# Scrum_Marquee.net
KiCad netlist of a schematic drawn in EAGLE
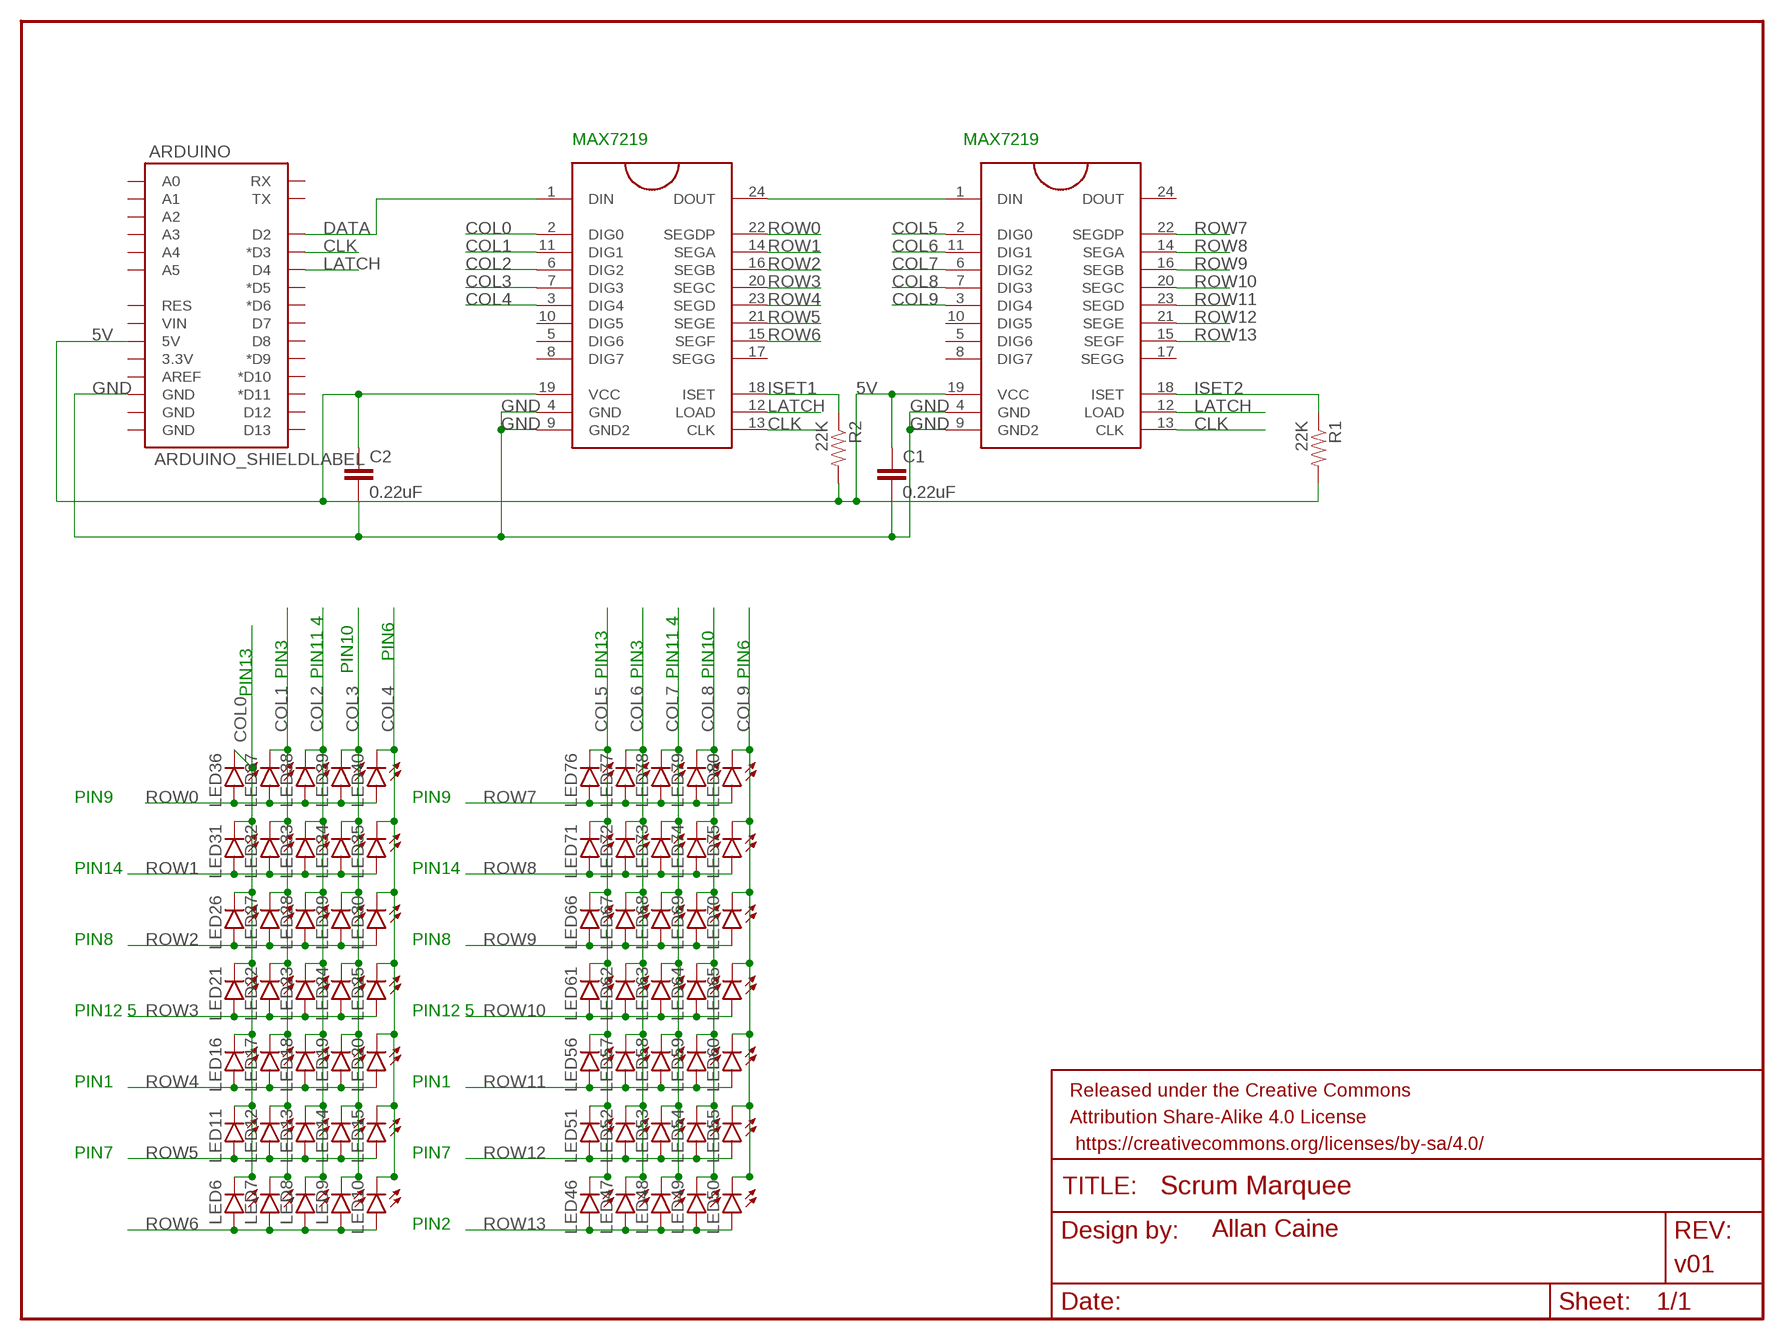
[diagram p0: schematic, sheet 1]

(export (version "E")
  (design (tool "Eeschema 10.0.6"))
  (components
    (comp (ref "ARDUINO")
      (value "ARDUINO_SHIELDLABEL")
      (footprint "eagle-import:DUEMILANOVE_SHIELD")
      (libsource (lib "eagle-import") (part "ARDUINO_SHIELDLABEL"))
    )
    (comp (ref "C1")
      (value "0.22uF")
      (footprint "eagle-import:CAP-PTH-SMALL-KIT")
      (libsource (lib "eagle-import") (part "0.1UF-50V-20%(PTH)KIT-EZ"))
    )
    (comp (ref "C2")
      (value "0.22uF")
      (footprint "eagle-import:CAP-PTH-SMALL-KIT")
      (libsource (lib "eagle-import") (part "0.1UF-50V-20%(PTH)KIT-EZ"))
    )
    (comp (ref "FRAME1")
      (value "FRAME-LETTER")
      (footprint "eagle-import:CREATIVE_COMMONS")
      (fields (field (name "DESIGNER") "Allan Caine"))
      (libsource (lib "eagle-import") (part "FRAME-LETTER"))
    )
    (comp (ref "LED6")
      (value "LED5MM")
      (footprint "eagle-import:LED5MM")
      (libsource (lib "eagle-import") (part "LED5MM"))
    )
    (comp (ref "LED7")
      (value "LED5MM")
      (footprint "eagle-import:LED5MM")
      (libsource (lib "eagle-import") (part "LED5MM"))
    )
    (comp (ref "LED8")
      (value "LED5MM")
      (footprint "eagle-import:LED5MM")
      (libsource (lib "eagle-import") (part "LED5MM"))
    )
    (comp (ref "LED9")
      (value "LED5MM")
      (footprint "eagle-import:LED5MM")
      (libsource (lib "eagle-import") (part "LED5MM"))
    )
    (comp (ref "LED10")
      (value "LED5MM")
      (footprint "eagle-import:LED5MM")
      (libsource (lib "eagle-import") (part "LED5MM"))
    )
    (comp (ref "LED11")
      (value "LED5MM")
      (footprint "eagle-import:LED5MM")
      (libsource (lib "eagle-import") (part "LED5MM"))
    )
    (comp (ref "LED12")
      (value "LED5MM")
      (footprint "eagle-import:LED5MM")
      (libsource (lib "eagle-import") (part "LED5MM"))
    )
    (comp (ref "LED13")
      (value "LED5MM")
      (footprint "eagle-import:LED5MM")
      (libsource (lib "eagle-import") (part "LED5MM"))
    )
    (comp (ref "LED14")
      (value "LED5MM")
      (footprint "eagle-import:LED5MM")
      (libsource (lib "eagle-import") (part "LED5MM"))
    )
    (comp (ref "LED15")
      (value "LED5MM")
      (footprint "eagle-import:LED5MM")
      (libsource (lib "eagle-import") (part "LED5MM"))
    )
    (comp (ref "LED16")
      (value "LED5MM")
      (footprint "eagle-import:LED5MM")
      (libsource (lib "eagle-import") (part "LED5MM"))
    )
    (comp (ref "LED17")
      (value "LED5MM")
      (footprint "eagle-import:LED5MM")
      (libsource (lib "eagle-import") (part "LED5MM"))
    )
    (comp (ref "LED18")
      (value "LED5MM")
      (footprint "eagle-import:LED5MM")
      (libsource (lib "eagle-import") (part "LED5MM"))
    )
    (comp (ref "LED19")
      (value "LED5MM")
      (footprint "eagle-import:LED5MM")
      (libsource (lib "eagle-import") (part "LED5MM"))
    )
    (comp (ref "LED20")
      (value "LED5MM")
      (footprint "eagle-import:LED5MM")
      (libsource (lib "eagle-import") (part "LED5MM"))
    )
    (comp (ref "LED21")
      (value "LED5MM")
      (footprint "eagle-import:LED5MM")
      (libsource (lib "eagle-import") (part "LED5MM"))
    )
    (comp (ref "LED22")
      (value "LED5MM")
      (footprint "eagle-import:LED5MM")
      (libsource (lib "eagle-import") (part "LED5MM"))
    )
    (comp (ref "LED23")
      (value "LED5MM")
      (footprint "eagle-import:LED5MM")
      (libsource (lib "eagle-import") (part "LED5MM"))
    )
    (comp (ref "LED24")
      (value "LED5MM")
      (footprint "eagle-import:LED5MM")
      (libsource (lib "eagle-import") (part "LED5MM"))
    )
    (comp (ref "LED25")
      (value "LED5MM")
      (footprint "eagle-import:LED5MM")
      (libsource (lib "eagle-import") (part "LED5MM"))
    )
    (comp (ref "LED26")
      (value "LED5MM")
      (footprint "eagle-import:LED5MM")
      (libsource (lib "eagle-import") (part "LED5MM"))
    )
    (comp (ref "LED27")
      (value "LED5MM")
      (footprint "eagle-import:LED5MM")
      (libsource (lib "eagle-import") (part "LED5MM"))
    )
    (comp (ref "LED28")
      (value "LED5MM")
      (footprint "eagle-import:LED5MM")
      (libsource (lib "eagle-import") (part "LED5MM"))
    )
    (comp (ref "LED29")
      (value "LED5MM")
      (footprint "eagle-import:LED5MM")
      (libsource (lib "eagle-import") (part "LED5MM"))
    )
    (comp (ref "LED30")
      (value "LED5MM")
      (footprint "eagle-import:LED5MM")
      (libsource (lib "eagle-import") (part "LED5MM"))
    )
    (comp (ref "LED31")
      (value "LED5MM")
      (footprint "eagle-import:LED5MM")
      (libsource (lib "eagle-import") (part "LED5MM"))
    )
    (comp (ref "LED32")
      (value "LED5MM")
      (footprint "eagle-import:LED5MM")
      (libsource (lib "eagle-import") (part "LED5MM"))
    )
    (comp (ref "LED33")
      (value "LED5MM")
      (footprint "eagle-import:LED5MM")
      (libsource (lib "eagle-import") (part "LED5MM"))
    )
    (comp (ref "LED34")
      (value "LED5MM")
      (footprint "eagle-import:LED5MM")
      (libsource (lib "eagle-import") (part "LED5MM"))
    )
    (comp (ref "LED35")
      (value "LED5MM")
      (footprint "eagle-import:LED5MM")
      (libsource (lib "eagle-import") (part "LED5MM"))
    )
    (comp (ref "LED36")
      (value "LED5MM")
      (footprint "eagle-import:LED5MM")
      (libsource (lib "eagle-import") (part "LED5MM"))
    )
    (comp (ref "LED37")
      (value "LED5MM")
      (footprint "eagle-import:LED5MM")
      (libsource (lib "eagle-import") (part "LED5MM"))
    )
    (comp (ref "LED38")
      (value "LED5MM")
      (footprint "eagle-import:LED5MM")
      (libsource (lib "eagle-import") (part "LED5MM"))
    )
    (comp (ref "LED39")
      (value "LED5MM")
      (footprint "eagle-import:LED5MM")
      (libsource (lib "eagle-import") (part "LED5MM"))
    )
    (comp (ref "LED40")
      (value "LED5MM")
      (footprint "eagle-import:LED5MM")
      (libsource (lib "eagle-import") (part "LED5MM"))
    )
    (comp (ref "LED46")
      (value "LED5MM")
      (footprint "eagle-import:LED5MM")
      (libsource (lib "eagle-import") (part "LED5MM"))
    )
    (comp (ref "LED47")
      (value "LED5MM")
      (footprint "eagle-import:LED5MM")
      (libsource (lib "eagle-import") (part "LED5MM"))
    )
    (comp (ref "LED48")
      (value "LED5MM")
      (footprint "eagle-import:LED5MM")
      (libsource (lib "eagle-import") (part "LED5MM"))
    )
    (comp (ref "LED49")
      (value "LED5MM")
      (footprint "eagle-import:LED5MM")
      (libsource (lib "eagle-import") (part "LED5MM"))
    )
    (comp (ref "LED50")
      (value "LED5MM")
      (footprint "eagle-import:LED5MM")
      (libsource (lib "eagle-import") (part "LED5MM"))
    )
    (comp (ref "LED51")
      (value "LED5MM")
      (footprint "eagle-import:LED5MM")
      (libsource (lib "eagle-import") (part "LED5MM"))
    )
    (comp (ref "LED52")
      (value "LED5MM")
      (footprint "eagle-import:LED5MM")
      (libsource (lib "eagle-import") (part "LED5MM"))
    )
    (comp (ref "LED53")
      (value "LED5MM")
      (footprint "eagle-import:LED5MM")
      (libsource (lib "eagle-import") (part "LED5MM"))
    )
    (comp (ref "LED54")
      (value "LED5MM")
      (footprint "eagle-import:LED5MM")
      (libsource (lib "eagle-import") (part "LED5MM"))
    )
    (comp (ref "LED55")
      (value "LED5MM")
      (footprint "eagle-import:LED5MM")
      (libsource (lib "eagle-import") (part "LED5MM"))
    )
    (comp (ref "LED56")
      (value "LED5MM")
      (footprint "eagle-import:LED5MM")
      (libsource (lib "eagle-import") (part "LED5MM"))
    )
    (comp (ref "LED57")
      (value "LED5MM")
      (footprint "eagle-import:LED5MM")
      (libsource (lib "eagle-import") (part "LED5MM"))
    )
    (comp (ref "LED58")
      (value "LED5MM")
      (footprint "eagle-import:LED5MM")
      (libsource (lib "eagle-import") (part "LED5MM"))
    )
    (comp (ref "LED59")
      (value "LED5MM")
      (footprint "eagle-import:LED5MM")
      (libsource (lib "eagle-import") (part "LED5MM"))
    )
    (comp (ref "LED60")
      (value "LED5MM")
      (footprint "eagle-import:LED5MM")
      (libsource (lib "eagle-import") (part "LED5MM"))
    )
    (comp (ref "LED61")
      (value "LED5MM")
      (footprint "eagle-import:LED5MM")
      (libsource (lib "eagle-import") (part "LED5MM"))
    )
    (comp (ref "LED62")
      (value "LED5MM")
      (footprint "eagle-import:LED5MM")
      (libsource (lib "eagle-import") (part "LED5MM"))
    )
    (comp (ref "LED63")
      (value "LED5MM")
      (footprint "eagle-import:LED5MM")
      (libsource (lib "eagle-import") (part "LED5MM"))
    )
    (comp (ref "LED64")
      (value "LED5MM")
      (footprint "eagle-import:LED5MM")
      (libsource (lib "eagle-import") (part "LED5MM"))
    )
    (comp (ref "LED65")
      (value "LED5MM")
      (footprint "eagle-import:LED5MM")
      (libsource (lib "eagle-import") (part "LED5MM"))
    )
    (comp (ref "LED66")
      (value "LED5MM")
      (footprint "eagle-import:LED5MM")
      (libsource (lib "eagle-import") (part "LED5MM"))
    )
    (comp (ref "LED67")
      (value "LED5MM")
      (footprint "eagle-import:LED5MM")
      (libsource (lib "eagle-import") (part "LED5MM"))
    )
    (comp (ref "LED68")
      (value "LED5MM")
      (footprint "eagle-import:LED5MM")
      (libsource (lib "eagle-import") (part "LED5MM"))
    )
    (comp (ref "LED69")
      (value "LED5MM")
      (footprint "eagle-import:LED5MM")
      (libsource (lib "eagle-import") (part "LED5MM"))
    )
    (comp (ref "LED70")
      (value "LED5MM")
      (footprint "eagle-import:LED5MM")
      (libsource (lib "eagle-import") (part "LED5MM"))
    )
    (comp (ref "LED71")
      (value "LED5MM")
      (footprint "eagle-import:LED5MM")
      (libsource (lib "eagle-import") (part "LED5MM"))
    )
    (comp (ref "LED72")
      (value "LED5MM")
      (footprint "eagle-import:LED5MM")
      (libsource (lib "eagle-import") (part "LED5MM"))
    )
    (comp (ref "LED73")
      (value "LED5MM")
      (footprint "eagle-import:LED5MM")
      (libsource (lib "eagle-import") (part "LED5MM"))
    )
    (comp (ref "LED74")
      (value "LED5MM")
      (footprint "eagle-import:LED5MM")
      (libsource (lib "eagle-import") (part "LED5MM"))
    )
    (comp (ref "LED75")
      (value "LED5MM")
      (footprint "eagle-import:LED5MM")
      (libsource (lib "eagle-import") (part "LED5MM"))
    )
    (comp (ref "LED76")
      (value "LED5MM")
      (footprint "eagle-import:LED5MM")
      (libsource (lib "eagle-import") (part "LED5MM"))
    )
    (comp (ref "LED77")
      (value "LED5MM")
      (footprint "eagle-import:LED5MM")
      (libsource (lib "eagle-import") (part "LED5MM"))
    )
    (comp (ref "LED78")
      (value "LED5MM")
      (footprint "eagle-import:LED5MM")
      (libsource (lib "eagle-import") (part "LED5MM"))
    )
    (comp (ref "LED79")
      (value "LED5MM")
      (footprint "eagle-import:LED5MM")
      (libsource (lib "eagle-import") (part "LED5MM"))
    )
    (comp (ref "LED80")
      (value "LED5MM")
      (footprint "eagle-import:LED5MM")
      (libsource (lib "eagle-import") (part "LED5MM"))
    )
    (comp (ref "MAX7219DIP")
      (value "MAX7219DIP")
      (footprint "eagle-import:DIL24")
      (libsource (lib "eagle-import") (part "MAX7219DIP"))
    )
    (comp (ref "R1")
      (value "22K")
      (footprint "eagle-import:AXIAL-0.4")
      (libsource (lib "eagle-import") (part "RESISTORPTH-1/4W"))
    )
    (comp (ref "R2")
      (value "22K")
      (footprint "eagle-import:AXIAL-0.4")
      (libsource (lib "eagle-import") (part "RESISTORPTH-1/4W"))
    )
    (comp (ref "U$2")
      (value "MAX7219DIP")
      (footprint "eagle-import:DIL24")
      (libsource (lib "eagle-import") (part "MAX7219DIP"))
    )
  )
  (nets
    (net (code "1") (name "/5V") (class "Default")
      (node (ref "ARDUINO") (pin "5V") (pinfunction "5V_5V") (pintype "bidirectional"))
      (node (ref "C1") (pin "1") (pinfunction "1_1") (pintype "passive"))
      (node (ref "C2") (pin "1") (pinfunction "1_1") (pintype "passive"))
      (node (ref "MAX7219DIP") (pin "19") (pinfunction "VCC_19") (pintype "bidirectional"))
      (node (ref "R1") (pin "P$2") (pinfunction "2_P$2") (pintype "passive"))
      (node (ref "R2") (pin "P$2") (pinfunction "2_P$2") (pintype "passive"))
      (node (ref "U$2") (pin "19") (pinfunction "VCC_19") (pintype "bidirectional"))
    )
    (net (code "2") (name "/CLK") (class "Default")
      (node (ref "ARDUINO") (pin "D3") (pinfunction "*D3_D3") (pintype "bidirectional"))
      (node (ref "MAX7219DIP") (pin "13") (pinfunction "CLK_13") (pintype "bidirectional"))
      (node (ref "U$2") (pin "13") (pinfunction "CLK_13") (pintype "bidirectional"))
    )
    (net (code "3") (name "/COL0") (class "Default")
      (node (ref "LED11") (pin "K") (pinfunction "C_K") (pintype "passive"))
      (node (ref "LED16") (pin "K") (pinfunction "C_K") (pintype "passive"))
      (node (ref "LED21") (pin "K") (pinfunction "C_K") (pintype "passive"))
      (node (ref "LED26") (pin "K") (pinfunction "C_K") (pintype "passive"))
      (node (ref "LED31") (pin "K") (pinfunction "C_K") (pintype "passive"))
      (node (ref "LED36") (pin "K") (pinfunction "C_K") (pintype "passive"))
      (node (ref "LED6") (pin "K") (pinfunction "C_K") (pintype "passive"))
      (node (ref "MAX7219DIP") (pin "2") (pinfunction "DIG0_2") (pintype "bidirectional"))
    )
    (net (code "4") (name "/COL1") (class "Default")
      (node (ref "LED12") (pin "K") (pinfunction "C_K") (pintype "passive"))
      (node (ref "LED17") (pin "K") (pinfunction "C_K") (pintype "passive"))
      (node (ref "LED22") (pin "K") (pinfunction "C_K") (pintype "passive"))
      (node (ref "LED27") (pin "K") (pinfunction "C_K") (pintype "passive"))
      (node (ref "LED32") (pin "K") (pinfunction "C_K") (pintype "passive"))
      (node (ref "LED37") (pin "K") (pinfunction "C_K") (pintype "passive"))
      (node (ref "LED7") (pin "K") (pinfunction "C_K") (pintype "passive"))
      (node (ref "MAX7219DIP") (pin "11") (pinfunction "DIG1_11") (pintype "bidirectional"))
    )
    (net (code "5") (name "/COL2") (class "Default")
      (node (ref "LED13") (pin "K") (pinfunction "C_K") (pintype "passive"))
      (node (ref "LED18") (pin "K") (pinfunction "C_K") (pintype "passive"))
      (node (ref "LED23") (pin "K") (pinfunction "C_K") (pintype "passive"))
      (node (ref "LED28") (pin "K") (pinfunction "C_K") (pintype "passive"))
      (node (ref "LED33") (pin "K") (pinfunction "C_K") (pintype "passive"))
      (node (ref "LED38") (pin "K") (pinfunction "C_K") (pintype "passive"))
      (node (ref "LED8") (pin "K") (pinfunction "C_K") (pintype "passive"))
      (node (ref "MAX7219DIP") (pin "6") (pinfunction "DIG2_6") (pintype "bidirectional"))
    )
    (net (code "6") (name "/COL3") (class "Default")
      (node (ref "LED14") (pin "K") (pinfunction "C_K") (pintype "passive"))
      (node (ref "LED19") (pin "K") (pinfunction "C_K") (pintype "passive"))
      (node (ref "LED24") (pin "K") (pinfunction "C_K") (pintype "passive"))
      (node (ref "LED29") (pin "K") (pinfunction "C_K") (pintype "passive"))
      (node (ref "LED34") (pin "K") (pinfunction "C_K") (pintype "passive"))
      (node (ref "LED39") (pin "K") (pinfunction "C_K") (pintype "passive"))
      (node (ref "LED9") (pin "K") (pinfunction "C_K") (pintype "passive"))
      (node (ref "MAX7219DIP") (pin "7") (pinfunction "DIG3_7") (pintype "bidirectional"))
    )
    (net (code "7") (name "/COL4") (class "Default")
      (node (ref "LED10") (pin "K") (pinfunction "C_K") (pintype "passive"))
      (node (ref "LED15") (pin "K") (pinfunction "C_K") (pintype "passive"))
      (node (ref "LED20") (pin "K") (pinfunction "C_K") (pintype "passive"))
      (node (ref "LED25") (pin "K") (pinfunction "C_K") (pintype "passive"))
      (node (ref "LED30") (pin "K") (pinfunction "C_K") (pintype "passive"))
      (node (ref "LED35") (pin "K") (pinfunction "C_K") (pintype "passive"))
      (node (ref "LED40") (pin "K") (pinfunction "C_K") (pintype "passive"))
      (node (ref "MAX7219DIP") (pin "3") (pinfunction "DIG4_3") (pintype "bidirectional"))
    )
    (net (code "8") (name "/COL5") (class "Default")
      (node (ref "LED46") (pin "K") (pinfunction "C_K") (pintype "passive"))
      (node (ref "LED51") (pin "K") (pinfunction "C_K") (pintype "passive"))
      (node (ref "LED56") (pin "K") (pinfunction "C_K") (pintype "passive"))
      (node (ref "LED61") (pin "K") (pinfunction "C_K") (pintype "passive"))
      (node (ref "LED66") (pin "K") (pinfunction "C_K") (pintype "passive"))
      (node (ref "LED71") (pin "K") (pinfunction "C_K") (pintype "passive"))
      (node (ref "LED76") (pin "K") (pinfunction "C_K") (pintype "passive"))
      (node (ref "U$2") (pin "2") (pinfunction "DIG0_2") (pintype "bidirectional"))
    )
    (net (code "9") (name "/COL6") (class "Default")
      (node (ref "LED47") (pin "K") (pinfunction "C_K") (pintype "passive"))
      (node (ref "LED52") (pin "K") (pinfunction "C_K") (pintype "passive"))
      (node (ref "LED57") (pin "K") (pinfunction "C_K") (pintype "passive"))
      (node (ref "LED62") (pin "K") (pinfunction "C_K") (pintype "passive"))
      (node (ref "LED67") (pin "K") (pinfunction "C_K") (pintype "passive"))
      (node (ref "LED72") (pin "K") (pinfunction "C_K") (pintype "passive"))
      (node (ref "LED77") (pin "K") (pinfunction "C_K") (pintype "passive"))
      (node (ref "U$2") (pin "11") (pinfunction "DIG1_11") (pintype "bidirectional"))
    )
    (net (code "10") (name "/COL7") (class "Default")
      (node (ref "LED48") (pin "K") (pinfunction "C_K") (pintype "passive"))
      (node (ref "LED53") (pin "K") (pinfunction "C_K") (pintype "passive"))
      (node (ref "LED58") (pin "K") (pinfunction "C_K") (pintype "passive"))
      (node (ref "LED63") (pin "K") (pinfunction "C_K") (pintype "passive"))
      (node (ref "LED68") (pin "K") (pinfunction "C_K") (pintype "passive"))
      (node (ref "LED73") (pin "K") (pinfunction "C_K") (pintype "passive"))
      (node (ref "LED78") (pin "K") (pinfunction "C_K") (pintype "passive"))
      (node (ref "U$2") (pin "6") (pinfunction "DIG2_6") (pintype "bidirectional"))
    )
    (net (code "11") (name "/COL8") (class "Default")
      (node (ref "LED49") (pin "K") (pinfunction "C_K") (pintype "passive"))
      (node (ref "LED54") (pin "K") (pinfunction "C_K") (pintype "passive"))
      (node (ref "LED59") (pin "K") (pinfunction "C_K") (pintype "passive"))
      (node (ref "LED64") (pin "K") (pinfunction "C_K") (pintype "passive"))
      (node (ref "LED69") (pin "K") (pinfunction "C_K") (pintype "passive"))
      (node (ref "LED74") (pin "K") (pinfunction "C_K") (pintype "passive"))
      (node (ref "LED79") (pin "K") (pinfunction "C_K") (pintype "passive"))
      (node (ref "U$2") (pin "7") (pinfunction "DIG3_7") (pintype "bidirectional"))
    )
    (net (code "12") (name "/COL9") (class "Default")
      (node (ref "LED50") (pin "K") (pinfunction "C_K") (pintype "passive"))
      (node (ref "LED55") (pin "K") (pinfunction "C_K") (pintype "passive"))
      (node (ref "LED60") (pin "K") (pinfunction "C_K") (pintype "passive"))
      (node (ref "LED65") (pin "K") (pinfunction "C_K") (pintype "passive"))
      (node (ref "LED70") (pin "K") (pinfunction "C_K") (pintype "passive"))
      (node (ref "LED75") (pin "K") (pinfunction "C_K") (pintype "passive"))
      (node (ref "LED80") (pin "K") (pinfunction "C_K") (pintype "passive"))
      (node (ref "U$2") (pin "3") (pinfunction "DIG4_3") (pintype "bidirectional"))
    )
    (net (code "13") (name "/DATA") (class "Default")
      (node (ref "ARDUINO") (pin "D2") (pinfunction "D2_D2") (pintype "bidirectional"))
      (node (ref "MAX7219DIP") (pin "1") (pinfunction "DIN_1") (pintype "bidirectional"))
    )
    (net (code "14") (name "/GND") (class "Default")
      (node (ref "ARDUINO") (pin "GND@2") (pinfunction "GND_GND@2") (pintype "bidirectional"))
      (node (ref "C1") (pin "2") (pinfunction "2_2") (pintype "passive"))
      (node (ref "C2") (pin "2") (pinfunction "2_2") (pintype "passive"))
      (node (ref "MAX7219DIP") (pin "4") (pinfunction "GND_4") (pintype "bidirectional"))
      (node (ref "MAX7219DIP") (pin "9") (pinfunction "GND2_9") (pintype "bidirectional"))
      (node (ref "U$2") (pin "4") (pinfunction "GND_4") (pintype "bidirectional"))
      (node (ref "U$2") (pin "9") (pinfunction "GND2_9") (pintype "bidirectional"))
    )
    (net (code "15") (name "/ISET1") (class "Default")
      (node (ref "MAX7219DIP") (pin "18") (pinfunction "ISET_18") (pintype "bidirectional"))
      (node (ref "R2") (pin "P$1") (pinfunction "1_P$1") (pintype "passive"))
    )
    (net (code "16") (name "/ISET2") (class "Default")
      (node (ref "R1") (pin "P$1") (pinfunction "1_P$1") (pintype "passive"))
      (node (ref "U$2") (pin "18") (pinfunction "ISET_18") (pintype "bidirectional"))
    )
    (net (code "17") (name "/LATCH") (class "Default")
      (node (ref "ARDUINO") (pin "D4") (pinfunction "D4_D4") (pintype "bidirectional"))
      (node (ref "MAX7219DIP") (pin "12") (pinfunction "LOAD_12") (pintype "bidirectional"))
      (node (ref "U$2") (pin "12") (pinfunction "LOAD_12") (pintype "bidirectional"))
    )
    (net (code "18") (name "/ROW0") (class "Default")
      (node (ref "LED36") (pin "A") (pinfunction "A_A") (pintype "passive"))
      (node (ref "LED37") (pin "A") (pinfunction "A_A") (pintype "passive"))
      (node (ref "LED38") (pin "A") (pinfunction "A_A") (pintype "passive"))
      (node (ref "LED39") (pin "A") (pinfunction "A_A") (pintype "passive"))
      (node (ref "LED40") (pin "A") (pinfunction "A_A") (pintype "passive"))
      (node (ref "MAX7219DIP") (pin "22") (pinfunction "SEGDP_22") (pintype "bidirectional"))
    )
    (net (code "19") (name "/ROW1") (class "Default")
      (node (ref "LED31") (pin "A") (pinfunction "A_A") (pintype "passive"))
      (node (ref "LED32") (pin "A") (pinfunction "A_A") (pintype "passive"))
      (node (ref "LED33") (pin "A") (pinfunction "A_A") (pintype "passive"))
      (node (ref "LED34") (pin "A") (pinfunction "A_A") (pintype "passive"))
      (node (ref "LED35") (pin "A") (pinfunction "A_A") (pintype "passive"))
      (node (ref "MAX7219DIP") (pin "14") (pinfunction "SEGA_14") (pintype "bidirectional"))
    )
    (net (code "20") (name "/ROW2") (class "Default")
      (node (ref "LED26") (pin "A") (pinfunction "A_A") (pintype "passive"))
      (node (ref "LED27") (pin "A") (pinfunction "A_A") (pintype "passive"))
      (node (ref "LED28") (pin "A") (pinfunction "A_A") (pintype "passive"))
      (node (ref "LED29") (pin "A") (pinfunction "A_A") (pintype "passive"))
      (node (ref "LED30") (pin "A") (pinfunction "A_A") (pintype "passive"))
      (node (ref "MAX7219DIP") (pin "16") (pinfunction "SEGB_16") (pintype "bidirectional"))
    )
    (net (code "21") (name "/ROW3") (class "Default")
      (node (ref "LED21") (pin "A") (pinfunction "A_A") (pintype "passive"))
      (node (ref "LED22") (pin "A") (pinfunction "A_A") (pintype "passive"))
      (node (ref "LED23") (pin "A") (pinfunction "A_A") (pintype "passive"))
      (node (ref "LED24") (pin "A") (pinfunction "A_A") (pintype "passive"))
      (node (ref "LED25") (pin "A") (pinfunction "A_A") (pintype "passive"))
      (node (ref "MAX7219DIP") (pin "20") (pinfunction "SEGC_20") (pintype "bidirectional"))
    )
    (net (code "22") (name "/ROW4") (class "Default")
      (node (ref "LED16") (pin "A") (pinfunction "A_A") (pintype "passive"))
      (node (ref "LED17") (pin "A") (pinfunction "A_A") (pintype "passive"))
      (node (ref "LED18") (pin "A") (pinfunction "A_A") (pintype "passive"))
      (node (ref "LED19") (pin "A") (pinfunction "A_A") (pintype "passive"))
      (node (ref "LED20") (pin "A") (pinfunction "A_A") (pintype "passive"))
      (node (ref "MAX7219DIP") (pin "23") (pinfunction "SEGD_23") (pintype "bidirectional"))
    )
    (net (code "23") (name "/ROW5") (class "Default")
      (node (ref "LED11") (pin "A") (pinfunction "A_A") (pintype "passive"))
      (node (ref "LED12") (pin "A") (pinfunction "A_A") (pintype "passive"))
      (node (ref "LED13") (pin "A") (pinfunction "A_A") (pintype "passive"))
      (node (ref "LED14") (pin "A") (pinfunction "A_A") (pintype "passive"))
      (node (ref "LED15") (pin "A") (pinfunction "A_A") (pintype "passive"))
      (node (ref "MAX7219DIP") (pin "21") (pinfunction "SEGE_21") (pintype "bidirectional"))
    )
    (net (code "24") (name "/ROW6") (class "Default")
      (node (ref "LED10") (pin "A") (pinfunction "A_A") (pintype "passive"))
      (node (ref "LED6") (pin "A") (pinfunction "A_A") (pintype "passive"))
      (node (ref "LED7") (pin "A") (pinfunction "A_A") (pintype "passive"))
      (node (ref "LED8") (pin "A") (pinfunction "A_A") (pintype "passive"))
      (node (ref "LED9") (pin "A") (pinfunction "A_A") (pintype "passive"))
      (node (ref "MAX7219DIP") (pin "15") (pinfunction "SEGF_15") (pintype "bidirectional"))
    )
    (net (code "25") (name "/ROW7") (class "Default")
      (node (ref "LED76") (pin "A") (pinfunction "A_A") (pintype "passive"))
      (node (ref "LED77") (pin "A") (pinfunction "A_A") (pintype "passive"))
      (node (ref "LED78") (pin "A") (pinfunction "A_A") (pintype "passive"))
      (node (ref "LED79") (pin "A") (pinfunction "A_A") (pintype "passive"))
      (node (ref "LED80") (pin "A") (pinfunction "A_A") (pintype "passive"))
      (node (ref "U$2") (pin "22") (pinfunction "SEGDP_22") (pintype "bidirectional"))
    )
    (net (code "26") (name "/ROW8") (class "Default")
      (node (ref "LED71") (pin "A") (pinfunction "A_A") (pintype "passive"))
      (node (ref "LED72") (pin "A") (pinfunction "A_A") (pintype "passive"))
      (node (ref "LED73") (pin "A") (pinfunction "A_A") (pintype "passive"))
      (node (ref "LED74") (pin "A") (pinfunction "A_A") (pintype "passive"))
      (node (ref "LED75") (pin "A") (pinfunction "A_A") (pintype "passive"))
      (node (ref "U$2") (pin "14") (pinfunction "SEGA_14") (pintype "bidirectional"))
    )
    (net (code "27") (name "/ROW9") (class "Default")
      (node (ref "LED66") (pin "A") (pinfunction "A_A") (pintype "passive"))
      (node (ref "LED67") (pin "A") (pinfunction "A_A") (pintype "passive"))
      (node (ref "LED68") (pin "A") (pinfunction "A_A") (pintype "passive"))
      (node (ref "LED69") (pin "A") (pinfunction "A_A") (pintype "passive"))
      (node (ref "LED70") (pin "A") (pinfunction "A_A") (pintype "passive"))
      (node (ref "U$2") (pin "16") (pinfunction "SEGB_16") (pintype "bidirectional"))
    )
    (net (code "28") (name "/ROW10") (class "Default")
      (node (ref "LED61") (pin "A") (pinfunction "A_A") (pintype "passive"))
      (node (ref "LED62") (pin "A") (pinfunction "A_A") (pintype "passive"))
      (node (ref "LED63") (pin "A") (pinfunction "A_A") (pintype "passive"))
      (node (ref "LED64") (pin "A") (pinfunction "A_A") (pintype "passive"))
      (node (ref "LED65") (pin "A") (pinfunction "A_A") (pintype "passive"))
      (node (ref "U$2") (pin "20") (pinfunction "SEGC_20") (pintype "bidirectional"))
    )
    (net (code "29") (name "/ROW11") (class "Default")
      (node (ref "LED56") (pin "A") (pinfunction "A_A") (pintype "passive"))
      (node (ref "LED57") (pin "A") (pinfunction "A_A") (pintype "passive"))
      (node (ref "LED58") (pin "A") (pinfunction "A_A") (pintype "passive"))
      (node (ref "LED59") (pin "A") (pinfunction "A_A") (pintype "passive"))
      (node (ref "LED60") (pin "A") (pinfunction "A_A") (pintype "passive"))
      (node (ref "U$2") (pin "23") (pinfunction "SEGD_23") (pintype "bidirectional"))
    )
    (net (code "30") (name "/ROW12") (class "Default")
      (node (ref "LED51") (pin "A") (pinfunction "A_A") (pintype "passive"))
      (node (ref "LED52") (pin "A") (pinfunction "A_A") (pintype "passive"))
      (node (ref "LED53") (pin "A") (pinfunction "A_A") (pintype "passive"))
      (node (ref "LED54") (pin "A") (pinfunction "A_A") (pintype "passive"))
      (node (ref "LED55") (pin "A") (pinfunction "A_A") (pintype "passive"))
      (node (ref "U$2") (pin "21") (pinfunction "SEGE_21") (pintype "bidirectional"))
    )
    (net (code "31") (name "/ROW13") (class "Default")
      (node (ref "LED46") (pin "A") (pinfunction "A_A") (pintype "passive"))
      (node (ref "LED47") (pin "A") (pinfunction "A_A") (pintype "passive"))
      (node (ref "LED48") (pin "A") (pinfunction "A_A") (pintype "passive"))
      (node (ref "LED49") (pin "A") (pinfunction "A_A") (pintype "passive"))
      (node (ref "LED50") (pin "A") (pinfunction "A_A") (pintype "passive"))
      (node (ref "U$2") (pin "15") (pinfunction "SEGF_15") (pintype "bidirectional"))
    )
    (net (code "32") (name "Net-(MAX7219DIP-DOUT)") (class "Default")
      (node (ref "MAX7219DIP") (pin "24") (pinfunction "DOUT_24") (pintype "bidirectional"))
      (node (ref "U$2") (pin "1") (pinfunction "DIN_1") (pintype "bidirectional"))
    )
    (net (code "33") (name "unconnected-(ARDUINO-*D5-PadD5)") (class "Default")
      (node (ref "ARDUINO") (pin "D5") (pinfunction "*D5_D5") (pintype "bidirectional"))
    )
    (net (code "34") (name "unconnected-(ARDUINO-*D6-PadD6)") (class "Default")
      (node (ref "ARDUINO") (pin "D6") (pinfunction "*D6_D6") (pintype "bidirectional"))
    )
    (net (code "35") (name "unconnected-(ARDUINO-*D9-PadD9)") (class "Default")
      (node (ref "ARDUINO") (pin "D9") (pinfunction "*D9_D9") (pintype "bidirectional"))
    )
    (net (code "36") (name "unconnected-(ARDUINO-*D10-PadD10)") (class "Default")
      (node (ref "ARDUINO") (pin "D10") (pinfunction "*D10_D10") (pintype "bidirectional"))
    )
    (net (code "37") (name "unconnected-(ARDUINO-*D11-PadD11)") (class "Default")
      (node (ref "ARDUINO") (pin "D11") (pinfunction "*D11_D11") (pintype "bidirectional"))
    )
    (net (code "38") (name "unconnected-(ARDUINO-GND-PadGND@0)") (class "Default")
      (node (ref "ARDUINO") (pin "GND@0") (pinfunction "GND_GND@0") (pintype "bidirectional"))
    )
    (net (code "39") (name "unconnected-(ARDUINO-GND-PadGND@1)") (class "Default")
      (node (ref "ARDUINO") (pin "GND@1") (pinfunction "GND_GND@1") (pintype "bidirectional"))
    )
    (net (code "40") (name "unconnected-(ARDUINO-Pad3.3V)") (class "Default")
      (node (ref "ARDUINO") (pin "3.3V") (pinfunction "3.3V_3.3V") (pintype "bidirectional"))
    )
    (net (code "41") (name "unconnected-(ARDUINO-PadA0)") (class "Default")
      (node (ref "ARDUINO") (pin "A0") (pinfunction "A0_A0") (pintype "bidirectional"))
    )
    (net (code "42") (name "unconnected-(ARDUINO-PadA1)") (class "Default")
      (node (ref "ARDUINO") (pin "A1") (pinfunction "A1_A1") (pintype "bidirectional"))
    )
    (net (code "43") (name "unconnected-(ARDUINO-PadA2)") (class "Default")
      (node (ref "ARDUINO") (pin "A2") (pinfunction "A2_A2") (pintype "bidirectional"))
    )
    (net (code "44") (name "unconnected-(ARDUINO-PadA3)") (class "Default")
      (node (ref "ARDUINO") (pin "A3") (pinfunction "A3_A3") (pintype "bidirectional"))
    )
    (net (code "45") (name "unconnected-(ARDUINO-PadA4)") (class "Default")
      (node (ref "ARDUINO") (pin "A4") (pinfunction "A4_A4") (pintype "bidirectional"))
    )
    (net (code "46") (name "unconnected-(ARDUINO-PadA5)") (class "Default")
      (node (ref "ARDUINO") (pin "A5") (pinfunction "A5_A5") (pintype "bidirectional"))
    )
    (net (code "47") (name "unconnected-(ARDUINO-PadAREF)") (class "Default")
      (node (ref "ARDUINO") (pin "AREF") (pinfunction "AREF_AREF") (pintype "bidirectional"))
    )
    (net (code "48") (name "unconnected-(ARDUINO-PadD7)") (class "Default")
      (node (ref "ARDUINO") (pin "D7") (pinfunction "D7_D7") (pintype "bidirectional"))
    )
    (net (code "49") (name "unconnected-(ARDUINO-PadD8)") (class "Default")
      (node (ref "ARDUINO") (pin "D8") (pinfunction "D8_D8") (pintype "bidirectional"))
    )
    (net (code "50") (name "unconnected-(ARDUINO-PadD12)") (class "Default")
      (node (ref "ARDUINO") (pin "D12") (pinfunction "D12_D12") (pintype "bidirectional"))
    )
    (net (code "51") (name "unconnected-(ARDUINO-PadD13)") (class "Default")
      (node (ref "ARDUINO") (pin "D13") (pinfunction "D13_D13") (pintype "bidirectional"))
    )
    (net (code "52") (name "unconnected-(ARDUINO-PadRES)") (class "Default")
      (node (ref "ARDUINO") (pin "RES") (pinfunction "RES_RES") (pintype "bidirectional"))
    )
    (net (code "53") (name "unconnected-(ARDUINO-PadRX)") (class "Default")
      (node (ref "ARDUINO") (pin "RX") (pinfunction "RX_RX") (pintype "bidirectional"))
    )
    (net (code "54") (name "unconnected-(ARDUINO-PadTX)") (class "Default")
      (node (ref "ARDUINO") (pin "TX") (pinfunction "TX_TX") (pintype "bidirectional"))
    )
    (net (code "55") (name "unconnected-(ARDUINO-PadVIN)") (class "Default")
      (node (ref "ARDUINO") (pin "VIN") (pinfunction "VIN_VIN") (pintype "bidirectional"))
    )
    (net (code "56") (name "unconnected-(MAX7219DIP-DIG5-Pad10)") (class "Default")
      (node (ref "MAX7219DIP") (pin "10") (pinfunction "DIG5_10") (pintype "bidirectional"))
    )
    (net (code "57") (name "unconnected-(MAX7219DIP-DIG6-Pad5)") (class "Default")
      (node (ref "MAX7219DIP") (pin "5") (pinfunction "DIG6_5") (pintype "bidirectional"))
    )
    (net (code "58") (name "unconnected-(MAX7219DIP-DIG7-Pad8)") (class "Default")
      (node (ref "MAX7219DIP") (pin "8") (pinfunction "DIG7_8") (pintype "bidirectional"))
    )
    (net (code "59") (name "unconnected-(MAX7219DIP-SEGG-Pad17)") (class "Default")
      (node (ref "MAX7219DIP") (pin "17") (pinfunction "SEGG_17") (pintype "bidirectional"))
    )
    (net (code "60") (name "unconnected-(U$2-DIG5-Pad10)") (class "Default")
      (node (ref "U$2") (pin "10") (pinfunction "DIG5_10") (pintype "bidirectional"))
    )
    (net (code "61") (name "unconnected-(U$2-DIG6-Pad5)") (class "Default")
      (node (ref "U$2") (pin "5") (pinfunction "DIG6_5") (pintype "bidirectional"))
    )
    (net (code "62") (name "unconnected-(U$2-DIG7-Pad8)") (class "Default")
      (node (ref "U$2") (pin "8") (pinfunction "DIG7_8") (pintype "bidirectional"))
    )
    (net (code "63") (name "unconnected-(U$2-DOUT-Pad24)") (class "Default")
      (node (ref "U$2") (pin "24") (pinfunction "DOUT_24") (pintype "bidirectional"))
    )
    (net (code "64") (name "unconnected-(U$2-SEGG-Pad17)") (class "Default")
      (node (ref "U$2") (pin "17") (pinfunction "SEGG_17") (pintype "bidirectional"))
    )
  )
)
